# ESP32_MCU.net
KiCad netlist of a schematic drawn in Altium Designer
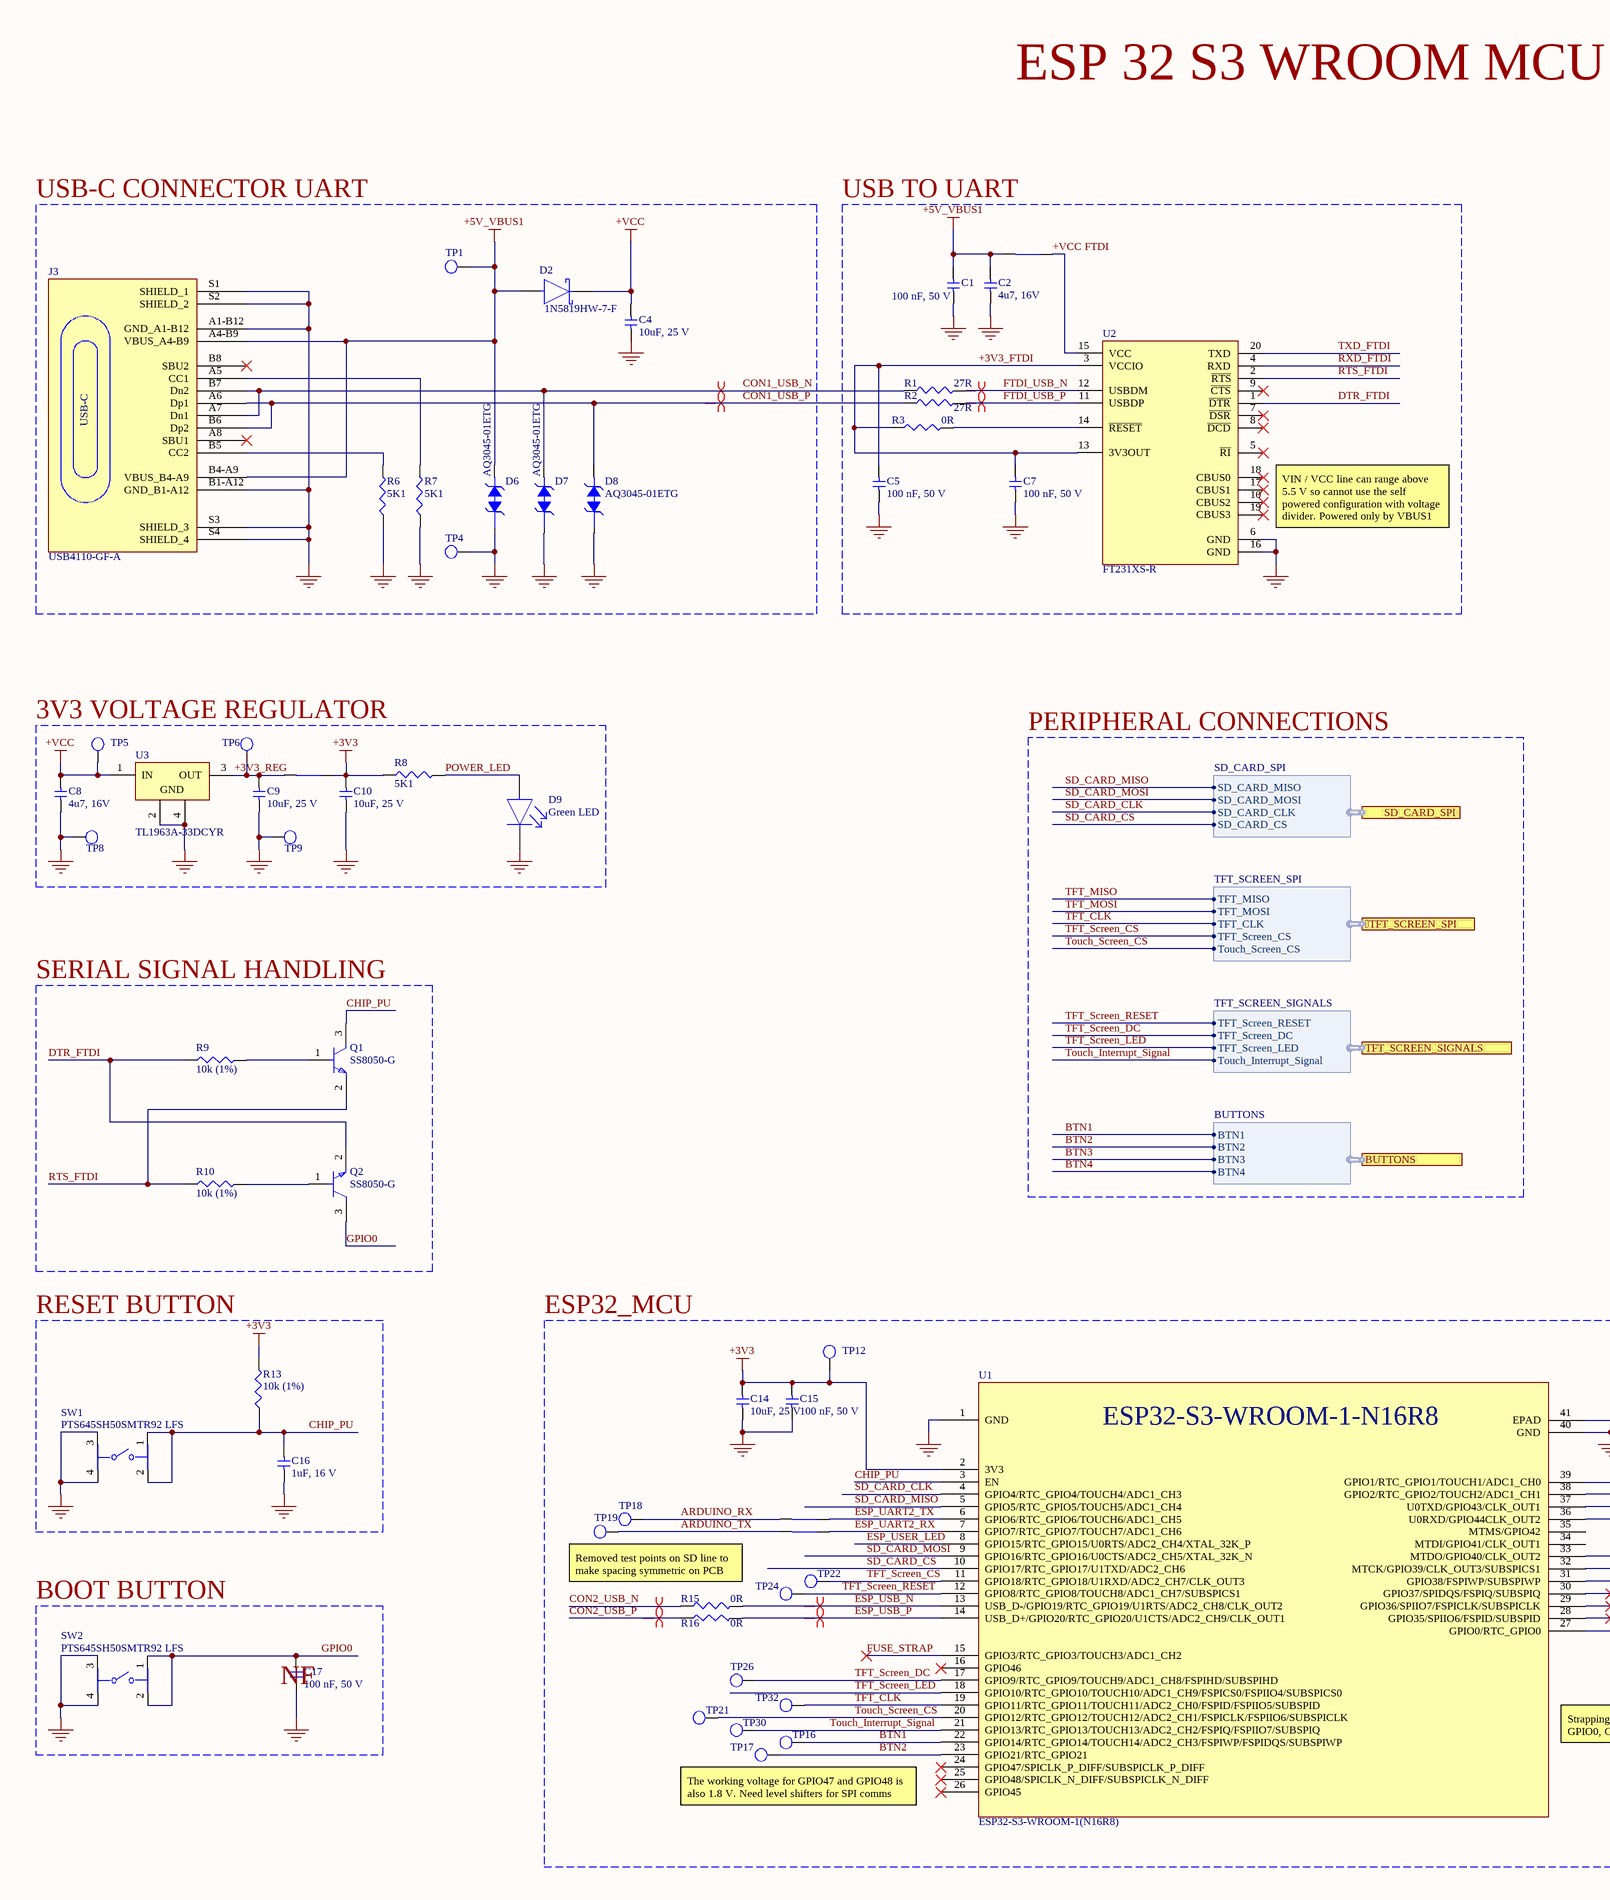
[diagram p0: ESP32_MCU.SchDoc, left]
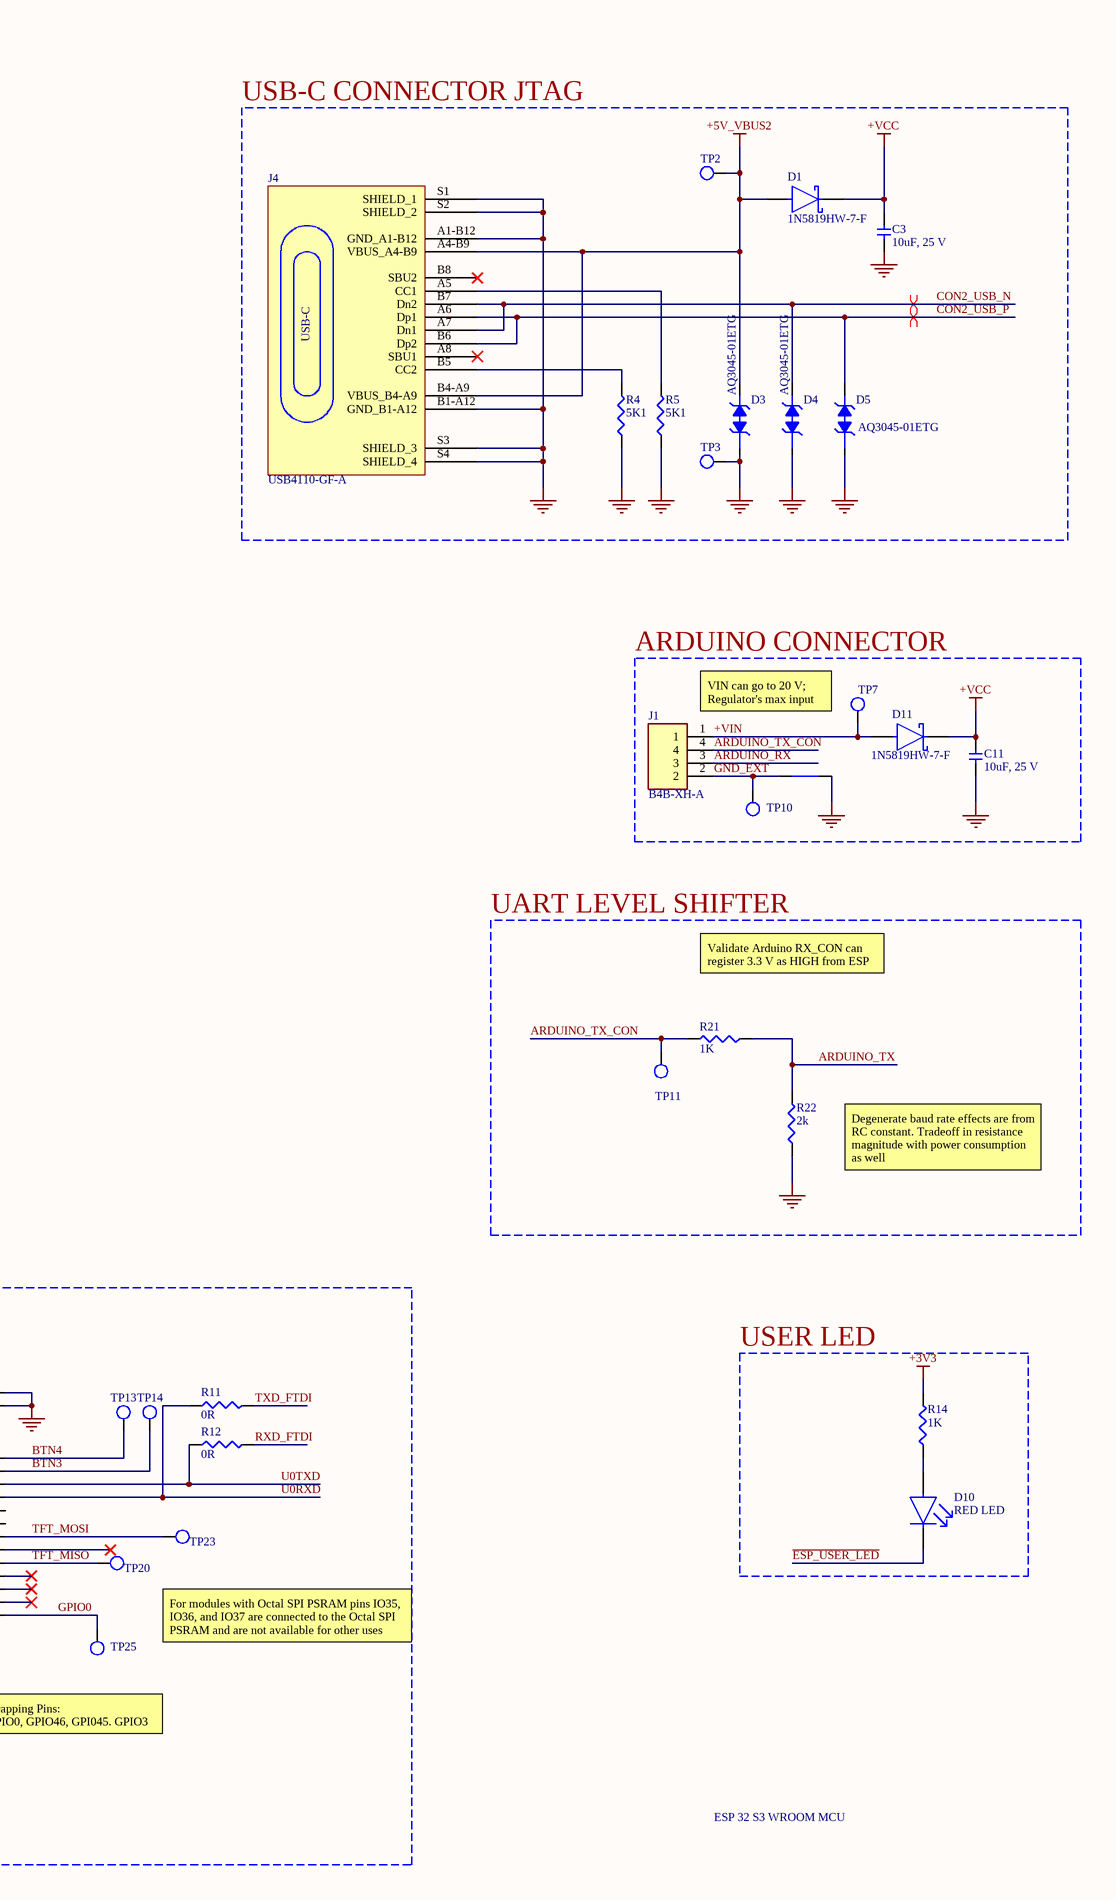
[diagram p1: ESP32_MCU.SchDoc, right]

(export (version "E")
  (design (tool "Eeschema 10.0.6"))
  (components
    (comp (ref "C1")
      (value "100 nF, 50 V")
      (footprint "0805_CAP")
      (fields
        (field (name "MANUFACTURER") "Walsin Technologies")
        (field (name "MANUFACTURER PART NUMBER") "1206B104K500CT")
      )
      (libsource (lib "SchLib") (part "1206B104K500CT"))
    )
    (comp (ref "C2")
      (value "4u7, 16V")
      (footprint "0805_CAP")
      (description "CAP CER 4.7UF 16V X7R 1206")
      (fields
        (field (name "MANUFACTURER") "Samsung")
        (field (name "MANUFACTURER PART NUMBER") "CL31B475KOHNNNE")
      )
      (libsource (lib "SchLib") (part "CL31B475KOHNNNE"))
    )
    (comp (ref "C3")
      (value "10uF, 25 V")
      (footprint "0805_CAP")
      (fields
        (field (name "MANUFACTURER") "Taiyo Yuden")
        (field (name "MANUFACTURER PART NUMBER") "TMK316BJ106KL-T")
      )
      (libsource (lib "SchLib") (part "TMK316BJ106KL-T"))
    )
    (comp (ref "C4")
      (value "10uF, 25 V")
      (footprint "0805_CAP")
      (fields
        (field (name "MANUFACTURER") "Taiyo Yuden")
        (field (name "MANUFACTURER PART NUMBER") "TMK316BJ106KL-T")
      )
      (libsource (lib "SchLib") (part "TMK316BJ106KL-T"))
    )
    (comp (ref "C5")
      (value "100 nF, 50 V")
      (footprint "0805_CAP")
      (fields
        (field (name "MANUFACTURER") "Walsin Technologies")
        (field (name "MANUFACTURER PART NUMBER") "1206B104K500CT")
      )
      (libsource (lib "SchLib") (part "1206B104K500CT"))
    )
    (comp (ref "C7")
      (value "100 nF, 50 V")
      (footprint "0805_CAP")
      (fields
        (field (name "MANUFACTURER") "Walsin Technologies")
        (field (name "MANUFACTURER PART NUMBER") "1206B104K500CT")
      )
      (libsource (lib "SchLib") (part "1206B104K500CT"))
    )
    (comp (ref "C8")
      (value "4u7, 16V")
      (footprint "0805_CAP")
      (description "CAP CER 4.7UF 16V X7R 1206")
      (fields
        (field (name "MANUFACTURER") "Samsung")
        (field (name "MANUFACTURER PART NUMBER") "CL31B475KOHNNNE")
      )
      (libsource (lib "SchLib") (part "CL31B475KOHNNNE"))
    )
    (comp (ref "C9")
      (value "10uF, 25 V")
      (footprint "0805_CAP")
      (fields
        (field (name "MANUFACTURER") "Taiyo Yuden")
        (field (name "MANUFACTURER PART NUMBER") "TMK316BJ106KL-T")
      )
      (libsource (lib "SchLib") (part "TMK316BJ106KL-T"))
    )
    (comp (ref "C10")
      (value "10uF, 25 V")
      (footprint "0805_CAP")
      (fields
        (field (name "MANUFACTURER") "Taiyo Yuden")
        (field (name "MANUFACTURER PART NUMBER") "TMK316BJ106KL-T")
      )
      (libsource (lib "SchLib") (part "TMK316BJ106KL-T"))
    )
    (comp (ref "C11")
      (value "10uF, 25 V")
      (footprint "0805_CAP")
      (fields
        (field (name "MANUFACTURER") "Taiyo Yuden")
        (field (name "MANUFACTURER PART NUMBER") "TMK316BJ106KL-T")
      )
      (libsource (lib "SchLib") (part "TMK316BJ106KL-T"))
    )
    (comp (ref "C14")
      (value "10uF, 25 V")
      (footprint "0805_CAP")
      (fields
        (field (name "MANUFACTURER") "Taiyo Yuden")
        (field (name "MANUFACTURER PART NUMBER") "TMK316BJ106KL-T")
      )
      (libsource (lib "SchLib") (part "TMK316BJ106KL-T"))
    )
    (comp (ref "C15")
      (value "100 nF, 50 V")
      (footprint "0805_CAP")
      (fields
        (field (name "MANUFACTURER") "Walsin Technologies")
        (field (name "MANUFACTURER PART NUMBER") "1206B104K500CT")
      )
      (libsource (lib "SchLib") (part "1206B104K500CT"))
    )
    (comp (ref "C16")
      (value "1uF, 16 V")
      (footprint "0805_CAP")
      (libsource (lib "SchLib") (part "CL31B105KOFNNNE"))
    )
    (comp (ref "C17")
      (value "100 nF, 50 V")
      (footprint "0805_CAP")
      (fields
        (field (name "MANUFACTURER") "Walsin Technologies")
        (field (name "MANUFACTURER PART NUMBER") "1206B104K500CT")
      )
      (libsource (lib "SchLib") (part "1206B104K500CT"))
    )
    (comp (ref "D1")
      (value "1N5819HW-7-F")
      (footprint "FP-SOD123-IPC_B")
      (description "Rectifier Diode, Schottky, 1 Phase, 1 Element, 1A, 40V V(RRM), Silicon")
      (fields (field (name "MANUFACTURER") "Diodes"))
      (libsource (lib "SchLib") (part "1N5819HW-7-F"))
    )
    (comp (ref "D2")
      (value "1N5819HW-7-F")
      (footprint "FP-SOD123-IPC_B")
      (description "Rectifier Diode, Schottky, 1 Phase, 1 Element, 1A, 40V V(RRM), Silicon")
      (fields (field (name "MANUFACTURER") "Diodes"))
      (libsource (lib "SchLib") (part "1N5819HW-7-F"))
    )
    (comp (ref "D3")
      (value "AQ3045-01ETG")
      (footprint "SOD882")
      (libsource (lib "SchLib") (part "AQ3045-01ETG"))
    )
    (comp (ref "D4")
      (value "AQ3045-01ETG")
      (footprint "SOD882")
      (libsource (lib "SchLib") (part "AQ3045-01ETG"))
    )
    (comp (ref "D5")
      (value "AQ3045-01ETG")
      (footprint "SOD882")
      (libsource (lib "SchLib") (part "AQ3045-01ETG"))
    )
    (comp (ref "D6")
      (value "AQ3045-01ETG")
      (footprint "SOD882")
      (libsource (lib "SchLib") (part "AQ3045-01ETG"))
    )
    (comp (ref "D7")
      (value "AQ3045-01ETG")
      (footprint "SOD882")
      (libsource (lib "SchLib") (part "AQ3045-01ETG"))
    )
    (comp (ref "D8")
      (value "AQ3045-01ETG")
      (footprint "SOD882")
      (libsource (lib "SchLib") (part "AQ3045-01ETG"))
    )
    (comp (ref "D9")
      (value "Green LED")
      (footprint "FP-LTST-C171KGKT-MFG")
      (description "Green 571nm LED Indication - Discrete 2V 0805 (2012 Metric)")
      (fields
        (field (name "MANUFACTURER") "Vishay Lite-On")
        (field (name "MANUFACTURER PART NUMBER") "LTST-C171KGKT")
      )
      (libsource (lib "SchLib") (part "LTST-C171KGKT"))
    )
    (comp (ref "D10")
      (value "RED LED")
      (footprint "LTST-C170KRKT_V")
      (description "Red 631nm LED Indication - Discrete 2V 0805 (2012 Metric)")
      (fields
        (field (name "MANUFACTURER") "Vishay Lite-On")
        (field (name "MANUFACTURER PART NUMBER") "LTST-C171KRKT")
      )
      (libsource (lib "SchLib") (part "LTST-C171KRKT"))
    )
    (comp (ref "D11")
      (value "1N5819HW-7-F")
      (footprint "FP-SOD123-IPC_B")
      (description "Rectifier Diode, Schottky, 1 Phase, 1 Element, 1A, 40V V(RRM), Silicon")
      (fields (field (name "MANUFACTURER") "Diodes"))
      (libsource (lib "SchLib") (part "1N5819HW-7-F"))
    )
    (comp (ref "J1")
      (value "B4B-XH-A")
      (footprint "JST_B4B-XH-A(LF)(SN)")
      (description "CONN HEADER VERT 4POS 2.5MM")
      (fields (field (name "MANUFACTURER") "JST") (field (name "MANUFACTURER PART NUMBER") "S4B-PH-K-S"))
      (libsource (lib "SchLib") (part "455-B4B-XH-A-ND"))
    )
    (comp (ref "J3")
      (value "USB4110-GF-A")
      (footprint "FP-USB4110-GF-A-MFG")
      (libsource (lib "SchLib") (part "USB4110-GF-A"))
    )
    (comp (ref "J4")
      (value "USB4110-GF-A")
      (footprint "FP-USB4110-GF-A-MFG")
      (libsource (lib "SchLib") (part "USB4110-GF-A"))
    )
    (comp (ref "NT1")
      (value "NT")
      (footprint "NetTie_SMD")
      (description "Net TIE SMD")
      (libsource (lib "SchLib") (part "NetTie_SMD"))
    )
    (comp (ref "NT2")
      (value "NT")
      (footprint "NetTie_SMD")
      (description "Net TIE SMD")
      (libsource (lib "SchLib") (part "NetTie_SMD"))
    )
    (comp (ref "NT3")
      (value "NT")
      (footprint "NetTie_SMD")
      (description "Net TIE SMD")
      (libsource (lib "SchLib") (part "NetTie_SMD"))
    )
    (comp (ref "NT6")
      (value "NT")
      (footprint "NetTie_SMD")
      (description "Net TIE SMD")
      (libsource (lib "SchLib") (part "NetTie_SMD"))
    )
    (comp (ref "NT8")
      (value "NT")
      (footprint "NetTie_SMD")
      (description "Net TIE SMD")
      (libsource (lib "SchLib") (part "NetTie_SMD"))
    )
    (comp (ref "Q1")
      (value "SS8050-G")
      (footprint "FP-SS8050-G-IPC_A")
      (description "Bipolar (BJT) Transistor NPN 25 V 1.5 A 100MHz 300 mW Surface Mount SOT-23-3")
      (fields (field (name "MANUFACTURER") "Comchip"))
      (libsource (lib "SchLib") (part "SS8050-G"))
    )
    (comp (ref "Q2")
      (value "SS8050-G")
      (footprint "FP-SS8050-G-IPC_A")
      (description "Bipolar (BJT) Transistor NPN 25 V 1.5 A 100MHz 300 mW Surface Mount SOT-23-3")
      (fields (field (name "MANUFACTURER") "Comchip"))
      (libsource (lib "SchLib") (part "SS8050-G"))
    )
    (comp (ref "R1")
      (value "27R")
      (footprint "0805_Resistor")
      (description "RES SMD 27.4 OHM 1% 1/8W 0805")
      (fields
        (field (name "MANUFACTURER") "Vishay")
        (field (name "MANUFACTURER PART NUMBER") "CRCW080527R4FKEA")
      )
      (libsource (lib "SchLib") (part "CRCW080527R4FKEA"))
    )
    (comp (ref "R2")
      (value "27R")
      (footprint "0805_Resistor")
      (description "RES SMD 27.4 OHM 1% 1/8W 0805")
      (fields
        (field (name "MANUFACTURER") "Vishay")
        (field (name "MANUFACTURER PART NUMBER") "CRCW080527R4FKEA")
      )
      (libsource (lib "SchLib") (part "CRCW080527R4FKEA"))
    )
    (comp (ref "R3")
      (value "0R")
      (footprint "0805_Resistor")
      (fields
        (field (name "MANUFACTURER") "Bourns")
        (field (name "MANUFACTURER PART NUMBER") "CR0805AJ/-000EAS")
      )
      (libsource (lib "SchLib") (part "CR0805AJ/-000EAS"))
    )
    (comp (ref "R4")
      (value "5K1")
      (footprint "0805_Resistor")
      (description "RES 5.1K OHM 5% 1/8W 0805")
      (fields (field (name "TOLERANCE") "5%") (field (name "MANUFACTURER") "Yageo"))
      (libsource (lib "SchLib") (part "RC0805JR-075K1L"))
    )
    (comp (ref "R5")
      (value "5K1")
      (footprint "0805_Resistor")
      (description "RES 5.1K OHM 5% 1/8W 0805")
      (fields (field (name "TOLERANCE") "5%") (field (name "MANUFACTURER") "Yageo"))
      (libsource (lib "SchLib") (part "RC0805JR-075K1L"))
    )
    (comp (ref "R6")
      (value "5K1")
      (footprint "0805_Resistor")
      (description "RES 5.1K OHM 5% 1/8W 0805")
      (fields (field (name "TOLERANCE") "5%") (field (name "MANUFACTURER") "Yageo"))
      (libsource (lib "SchLib") (part "RC0805JR-075K1L"))
    )
    (comp (ref "R7")
      (value "5K1")
      (footprint "0805_Resistor")
      (description "RES 5.1K OHM 5% 1/8W 0805")
      (fields (field (name "TOLERANCE") "5%") (field (name "MANUFACTURER") "Yageo"))
      (libsource (lib "SchLib") (part "RC0805JR-075K1L"))
    )
    (comp (ref "R8")
      (value "5K1")
      (footprint "0805_Resistor")
      (description "RES 5.1K OHM 5% 1/8W 0805")
      (fields
        (field (name "MANUFACTURER") "Yageo")
        (field (name "MANUFACTURER PART NUMBER") "RC0805JR-075K1L")
      )
      (libsource (lib "SchLib") (part "RC0805JR-075K1L"))
    )
    (comp (ref "R9")
      (value "10k (1%)")
      (footprint "0805_Resistor")
      (fields (field (name "TOLERANCE") "1%"))
      (libsource (lib "SchLib") (part "RMCF0805FT10K0"))
    )
    (comp (ref "R10")
      (value "10k (1%)")
      (footprint "0805_Resistor")
      (fields (field (name "TOLERANCE") "1%"))
      (libsource (lib "SchLib") (part "RMCF0805FT10K0"))
    )
    (comp (ref "R11")
      (value "0R")
      (footprint "0805_Resistor")
      (fields
        (field (name "MANUFACTURER") "Bourns")
        (field (name "MANUFACTURER PART NUMBER") "CR0805AJ/-000EAS")
      )
      (libsource (lib "SchLib") (part "CR0805AJ/-000EAS"))
    )
    (comp (ref "R12")
      (value "0R")
      (footprint "0805_Resistor")
      (fields
        (field (name "MANUFACTURER") "Bourns")
        (field (name "MANUFACTURER PART NUMBER") "CR0805AJ/-000EAS")
      )
      (libsource (lib "SchLib") (part "CR0805AJ/-000EAS"))
    )
    (comp (ref "R13")
      (value "10k (1%)")
      (footprint "0805_Resistor")
      (fields (field (name "TOLERANCE") "1%"))
      (libsource (lib "SchLib") (part "RMCF0805FT10K0"))
    )
    (comp (ref "R14")
      (value "1K")
      (footprint "0805_Resistor")
      (description "RES 1K OHM 1% 1/8W 0805")
      (fields
        (field (name "MANUFACTURER") "Yageo")
        (field (name "MANUFACTURER PART NUMBER") "RC0805FR-071KL")
      )
      (libsource (lib "SchLib") (part "RC0805FR-071KL"))
    )
    (comp (ref "R15")
      (value "0R")
      (footprint "0805_Resistor")
      (fields
        (field (name "MANUFACTURER") "Bourns")
        (field (name "MANUFACTURER PART NUMBER") "CR0805AJ/-000EAS")
      )
      (libsource (lib "SchLib") (part "CR0805AJ/-000EAS"))
    )
    (comp (ref "R16")
      (value "0R")
      (footprint "0805_Resistor")
      (fields
        (field (name "MANUFACTURER") "Bourns")
        (field (name "MANUFACTURER PART NUMBER") "CR0805AJ/-000EAS")
      )
      (libsource (lib "SchLib") (part "CR0805AJ/-000EAS"))
    )
    (comp (ref "R21")
      (value "1K")
      (footprint "0805_Resistor")
      (description "RES 1K OHM 1% 1/8W 0805")
      (fields
        (field (name "MANUFACTURER") "Yageo")
        (field (name "MANUFACTURER PART NUMBER") "RC0805FR-071KL")
      )
      (libsource (lib "SchLib") (part "RC0805FR-071KL"))
    )
    (comp (ref "R22")
      (value "2k")
      (footprint "0805_Resistor")
      (fields
        (field (name "MANUFACTURER") "Vishay")
        (field (name "MANUFACTURER PART NUMBER") "CRCW08052K00FKEA")
        (field (name "TOLERANCE") "1%")
      )
      (libsource (lib "SchLib") (part "CRCW08052K00FKEA"))
    )
    (comp (ref "SW1")
      (value "PTS645SH50SMTR92 LFS")
      (footprint "FP-PTS645SH50SMTR92LFS-MFG")
      (description "Tactile Switch SPST-NO Top Actuated Surface Mount")
      (libsource (lib "SchLib") (part "PTS645SH50SMTR92 LFS"))
    )
    (comp (ref "SW2")
      (value "PTS645SH50SMTR92 LFS")
      (footprint "FP-PTS645SH50SMTR92LFS-MFG")
      (description "Tactile Switch SPST-NO Top Actuated Surface Mount")
      (libsource (lib "SchLib") (part "PTS645SH50SMTR92 LFS"))
    )
    (comp (ref "TP1")
      (value "Test Point")
      (footprint "Probe-Point")
      (description "Generic Test Point")
      (libsource (lib "University of Calgary Solar Car Team") (part "Test Point-Symbol-1"))
    )
    (comp (ref "TP2")
      (value "Test Point")
      (footprint "Probe-Point")
      (description "Generic Test Point")
      (libsource (lib "University of Calgary Solar Car Team") (part "Test Point-Symbol-1"))
    )
    (comp (ref "TP3")
      (value "Test Point")
      (footprint "Probe-Point")
      (description "Generic Test Point")
      (libsource (lib "University of Calgary Solar Car Team") (part "Test Point-Symbol-1"))
    )
    (comp (ref "TP4")
      (value "Test Point")
      (footprint "Probe-Point")
      (description "Generic Test Point")
      (libsource (lib "University of Calgary Solar Car Team") (part "Test Point-Symbol-1"))
    )
    (comp (ref "TP5")
      (value "Test Point")
      (footprint "Probe-Point")
      (description "Generic Test Point")
      (libsource (lib "University of Calgary Solar Car Team") (part "Test Point-Symbol-1"))
    )
    (comp (ref "TP6")
      (value "Test Point")
      (footprint "Probe-Point")
      (description "Generic Test Point")
      (libsource (lib "University of Calgary Solar Car Team") (part "Test Point-Symbol-1"))
    )
    (comp (ref "TP7")
      (value "Test Point")
      (footprint "Probe-Point")
      (description "Generic Test Point")
      (libsource (lib "University of Calgary Solar Car Team") (part "Test Point-Symbol-1"))
    )
    (comp (ref "TP8")
      (value "Test Point")
      (footprint "Probe-Point")
      (description "Generic Test Point")
      (libsource (lib "University of Calgary Solar Car Team") (part "Test Point-Symbol-1"))
    )
    (comp (ref "TP9")
      (value "Test Point")
      (footprint "Probe-Point")
      (description "Generic Test Point")
      (libsource (lib "University of Calgary Solar Car Team") (part "Test Point-Symbol-1"))
    )
    (comp (ref "TP10")
      (value "Test Point")
      (footprint "Probe-Point")
      (description "Generic Test Point")
      (libsource (lib "University of Calgary Solar Car Team") (part "Test Point-Symbol-1"))
    )
    (comp (ref "TP11")
      (value "Test Point")
      (footprint "Probe-Point")
      (description "Generic Test Point")
      (libsource (lib "University of Calgary Solar Car Team") (part "Test Point-Symbol-1"))
    )
    (comp (ref "TP12")
      (value "Test Point")
      (footprint "Probe-Point")
      (description "Generic Test Point")
      (libsource (lib "University of Calgary Solar Car Team") (part "Test Point-Symbol-1"))
    )
    (comp (ref "TP13")
      (value "Test Point")
      (footprint "Probe-Point")
      (description "Generic Test Point")
      (libsource (lib "University of Calgary Solar Car Team") (part "Test Point-Symbol-1"))
    )
    (comp (ref "TP14")
      (value "Test Point")
      (footprint "Probe-Point")
      (description "Generic Test Point")
      (libsource (lib "University of Calgary Solar Car Team") (part "Test Point-Symbol-1"))
    )
    (comp (ref "TP16")
      (value "Test Point")
      (footprint "Probe-Point")
      (description "Generic Test Point")
      (libsource (lib "University of Calgary Solar Car Team") (part "Test Point-Symbol-1"))
    )
    (comp (ref "TP17")
      (value "Test Point")
      (footprint "Probe-Point")
      (description "Generic Test Point")
      (libsource (lib "University of Calgary Solar Car Team") (part "Test Point-Symbol-1"))
    )
    (comp (ref "TP18")
      (value "Test Point")
      (footprint "Probe-Point")
      (description "Generic Test Point")
      (libsource (lib "University of Calgary Solar Car Team") (part "Test Point-Symbol-1"))
    )
    (comp (ref "TP19")
      (value "Test Point")
      (footprint "Probe-Point")
      (description "Generic Test Point")
      (libsource (lib "University of Calgary Solar Car Team") (part "Test Point-Symbol-1"))
    )
    (comp (ref "TP20")
      (value "Test Point")
      (footprint "Probe-Point")
      (description "Generic Test Point")
      (libsource (lib "University of Calgary Solar Car Team") (part "Test Point-Symbol-1"))
    )
    (comp (ref "TP21")
      (value "Test Point")
      (footprint "Probe-Point")
      (description "Generic Test Point")
      (libsource (lib "University of Calgary Solar Car Team") (part "Test Point-Symbol-1"))
    )
    (comp (ref "TP22")
      (value "Test Point")
      (footprint "Probe-Point")
      (description "Generic Test Point")
      (libsource (lib "University of Calgary Solar Car Team") (part "Test Point-Symbol-1"))
    )
    (comp (ref "TP23")
      (value "Test Point")
      (footprint "Probe-Point")
      (description "Generic Test Point")
      (libsource (lib "University of Calgary Solar Car Team") (part "Test Point-Symbol-1"))
    )
    (comp (ref "TP24")
      (value "Test Point")
      (footprint "Probe-Point")
      (description "Generic Test Point")
      (libsource (lib "University of Calgary Solar Car Team") (part "Test Point-Symbol-1"))
    )
    (comp (ref "TP25")
      (value "Test Point")
      (footprint "Probe-Point")
      (description "Generic Test Point")
      (libsource (lib "University of Calgary Solar Car Team") (part "Test Point-Symbol-1"))
    )
    (comp (ref "TP26")
      (value "Test Point")
      (footprint "Probe-Point")
      (description "Generic Test Point")
      (libsource (lib "University of Calgary Solar Car Team") (part "Test Point-Symbol-1"))
    )
    (comp (ref "TP30")
      (value "Test Point")
      (footprint "Probe-Point")
      (description "Generic Test Point")
      (libsource (lib "University of Calgary Solar Car Team") (part "Test Point-Symbol-1"))
    )
    (comp (ref "TP32")
      (value "Test Point")
      (footprint "Probe-Point")
      (description "Generic Test Point")
      (libsource (lib "University of Calgary Solar Car Team") (part "Test Point-Symbol-1"))
    )
    (comp (ref "U1")
      (value "ESP32-S3-WROOM-1(N16R8)")
      (footprint "ESP32S3WROOM1N8R2")
      (description "RF TXRX MOD BT WIFI PCB TH SMD")
      (fields (field (name "MANUFACTURER") "Espressif Systems"))
      (libsource (lib "SchLib") (part "ESP32-S3-WROOM-1(N16R8)"))
    )
    (comp (ref "U2")
      (value "FT231XS-R")
      (footprint "FP-SSOP-20-IPC_A")
      (description "IC USB SERIAL FULL UART 20SSOP")
      (fields (field (name "MANUFACTURER") "FTDI"))
      (libsource (lib "SchLib") (part "FT231XS-R"))
    )
    (comp (ref "U3")
      (value "TL1963A-33DCYR")
      (footprint "DCY0004A_N")
      (description "Linear Voltage Regulator IC Positive Fixed 1 Output 1.5A SOT-223-4")
      (fields (field (name "MANUFACTURER") "Texas Instruments"))
      (libsource (lib "SchLib") (part "TL1963A-33DCYR"))
    )
  )
  (nets
    (net (code "5") (name "+3V3") (class "Default")
      (node (ref "C10") (pin "2") (pinfunction "2_2") (pintype "passive"))
      (node (ref "C14") (pin "2") (pinfunction "2_2") (pintype "passive"))
      (node (ref "C15") (pin "2") (pinfunction "2_2") (pintype "passive"))
      (node (ref "NT3") (pin "2") (pinfunction "10_2") (pintype "passive"))
      (node (ref "R13") (pin "2") (pinfunction "2_2") (pintype "passive"))
      (node (ref "R14") (pin "2") (pinfunction "2_2") (pintype "passive"))
      (node (ref "R8") (pin "1") (pinfunction "1_1") (pintype "passive"))
      (node (ref "TP12") (pin "1") (pinfunction "1_1") (pintype "passive"))
      (node (ref "U1") (pin "2") (pinfunction "3V3_2") (pintype "passive"))
    )
    (net (code "6") (name "+5V_VBUS1") (class "Default")
      (node (ref "C1") (pin "2") (pinfunction "2_2") (pintype "passive"))
      (node (ref "C2") (pin "2") (pinfunction "2_2") (pintype "passive"))
      (node (ref "D2") (pin "2") (pinfunction "A_2") (pintype "passive"))
      (node (ref "D6") (pin "1") (pinfunction "1_1") (pintype "passive"))
      (node (ref "J3") (pin "A4-B9") (pinfunction "VBUS_A4-B9_A4-B9") (pintype "passive"))
      (node (ref "J3") (pin "B4-A9") (pinfunction "VBUS_B4-A9_B4-A9") (pintype "passive"))
      (node (ref "NT6") (pin "1") (pinfunction "9_1") (pintype "passive"))
      (node (ref "TP1") (pin "1") (pinfunction "1_1") (pintype "passive"))
    )
    (net (code "7") (name "+5V_VBUS2") (class "Default")
      (node (ref "D1") (pin "2") (pinfunction "A_2") (pintype "passive"))
      (node (ref "D3") (pin "1") (pinfunction "1_1") (pintype "passive"))
      (node (ref "J4") (pin "A4-B9") (pinfunction "VBUS_A4-B9_A4-B9") (pintype "passive"))
      (node (ref "J4") (pin "B4-A9") (pinfunction "VBUS_B4-A9_B4-A9") (pintype "passive"))
      (node (ref "TP2") (pin "1") (pinfunction "1_1") (pintype "passive"))
    )
    (net (code "8") (name "+VCC") (class "Default")
      (node (ref "C11") (pin "2") (pinfunction "2_2") (pintype "passive"))
      (node (ref "C3") (pin "2") (pinfunction "2_2") (pintype "passive"))
      (node (ref "C4") (pin "2") (pinfunction "2_2") (pintype "passive"))
      (node (ref "C8") (pin "2") (pinfunction "2_2") (pintype "passive"))
      (node (ref "D1") (pin "1") (pinfunction "C_1") (pintype "passive"))
      (node (ref "D11") (pin "1") (pinfunction "C_1") (pintype "passive"))
      (node (ref "D2") (pin "1") (pinfunction "C_1") (pintype "passive"))
      (node (ref "TP5") (pin "1") (pinfunction "1_1") (pintype "passive"))
      (node (ref "U3") (pin "1") (pinfunction "IN_1") (pintype "power_in"))
    )
    (net (code "9") (name "/+3V3_FTDI") (class "Default")
      (node (ref "C5") (pin "2") (pinfunction "2_2") (pintype "passive"))
      (node (ref "C7") (pin "2") (pinfunction "2_2") (pintype "passive"))
      (node (ref "R3") (pin "1") (pinfunction "1_1") (pintype "passive"))
      (node (ref "U2") (pin "13") (pinfunction "3V3OUT_13") (pintype "passive"))
      (node (ref "U2") (pin "3") (pinfunction "VCCIO_3") (pintype "passive"))
    )
    (net (code "10") (name "/+3V3_REG") (class "Default")
      (node (ref "C9") (pin "2") (pinfunction "2_2") (pintype "passive"))
      (node (ref "NT3") (pin "1") (pinfunction "9_1") (pintype "passive"))
      (node (ref "TP6") (pin "1") (pinfunction "1_1") (pintype "passive"))
      (node (ref "U3") (pin "3") (pinfunction "OUT_3") (pintype "power_in"))
    )
    (net (code "11") (name "/+VCC FTDI") (class "Default")
      (node (ref "NT6") (pin "2") (pinfunction "10_2") (pintype "passive"))
      (node (ref "U2") (pin "15") (pinfunction "VCC_15") (pintype "passive"))
    )
    (net (code "12") (name "/+VIN") (class "Default")
      (node (ref "D11") (pin "2") (pinfunction "A_2") (pintype "passive"))
      (node (ref "J1") (pin "1") (pinfunction "1_1") (pintype "passive"))
      (node (ref "TP7") (pin "1") (pinfunction "1_1") (pintype "passive"))
    )
    (net (code "13") (name "/ARDUINO_RX") (class "Default")
      (node (ref "J1") (pin "3") (pinfunction "3_3") (pintype "passive"))
      (node (ref "NT1") (pin "1") (pinfunction "9_1") (pintype "passive"))
      (node (ref "TP18") (pin "1") (pinfunction "1_1") (pintype "passive"))
    )
    (net (code "14") (name "/ARDUINO_TX") (class "Default")
      (node (ref "NT2") (pin "1") (pinfunction "9_1") (pintype "passive"))
      (node (ref "R21") (pin "1") (pinfunction "1_1") (pintype "passive"))
      (node (ref "R22") (pin "2") (pinfunction "2_2") (pintype "passive"))
      (node (ref "TP19") (pin "1") (pinfunction "1_1") (pintype "passive"))
    )
    (net (code "15") (name "/ARDUINO_TX_CON") (class "Default")
      (node (ref "J1") (pin "4") (pinfunction "4_4") (pintype "passive"))
      (node (ref "R21") (pin "2") (pinfunction "2_2") (pintype "passive"))
      (node (ref "TP11") (pin "1") (pinfunction "1_1") (pintype "passive"))
    )
    (net (code "16") (name "/BTN1") (class "Default")
      (node (ref "TP16") (pin "1") (pinfunction "1_1") (pintype "passive"))
      (node (ref "U1") (pin "22") (pinfunction "GPIO14/RTC_GPIO14/TOUCH14/ADC2_CH3/FSPIWP/FSPIDQS/SUBSPIWP_22") (pintype "passive"))
    )
    (net (code "17") (name "/BTN2") (class "Default")
      (node (ref "TP17") (pin "1") (pinfunction "1_1") (pintype "passive"))
      (node (ref "U1") (pin "23") (pinfunction "GPIO21/RTC_GPIO21_23") (pintype "passive"))
    )
    (net (code "18") (name "/BTN3") (class "Default")
      (node (ref "TP14") (pin "1") (pinfunction "1_1") (pintype "passive"))
      (node (ref "U1") (pin "38") (pinfunction "GPIO2/RTC_GPIO2/TOUCH2/ADC1_CH1_38") (pintype "passive"))
    )
    (net (code "19") (name "/BTN4") (class "Default")
      (node (ref "TP13") (pin "1") (pinfunction "1_1") (pintype "passive"))
      (node (ref "U1") (pin "39") (pinfunction "GPIO1/RTC_GPIO1/TOUCH1/ADC1_CH0_39") (pintype "passive"))
    )
    (net (code "20") (name "/CHIP_PU") (class "Default")
      (node (ref "C16") (pin "2") (pinfunction "2_2") (pintype "passive"))
      (node (ref "Q1") (pin "3") (pinfunction "C_3") (pintype "passive"))
      (node (ref "R13") (pin "1") (pinfunction "1_1") (pintype "passive"))
      (node (ref "SW1") (pin "1") (pinfunction "1_1") (pintype "passive"))
      (node (ref "SW1") (pin "2") (pinfunction "2_2") (pintype "passive"))
      (node (ref "U1") (pin "3") (pinfunction "EN_3") (pintype "passive"))
    )
    (net (code "21") (name "/CON1_USB_N") (class "Default")
      (node (ref "D7") (pin "1") (pinfunction "1_1") (pintype "passive"))
      (node (ref "J3") (pin "A7") (pinfunction "Dn1_A7") (pintype "passive"))
      (node (ref "J3") (pin "B7") (pinfunction "Dn2_B7") (pintype "passive"))
      (node (ref "R1") (pin "1") (pinfunction "1_1") (pintype "passive"))
    )
    (net (code "22") (name "/CON1_USB_P") (class "Default")
      (node (ref "D8") (pin "1") (pinfunction "1_1") (pintype "passive"))
      (node (ref "J3") (pin "A6") (pinfunction "Dp1_A6") (pintype "passive"))
      (node (ref "J3") (pin "B6") (pinfunction "Dp2_B6") (pintype "passive"))
      (node (ref "R2") (pin "1") (pinfunction "1_1") (pintype "passive"))
    )
    (net (code "23") (name "/CON2_USB_N") (class "Default")
      (node (ref "D4") (pin "1") (pinfunction "1_1") (pintype "passive"))
      (node (ref "J4") (pin "A7") (pinfunction "Dn1_A7") (pintype "passive"))
      (node (ref "J4") (pin "B7") (pinfunction "Dn2_B7") (pintype "passive"))
      (node (ref "R15") (pin "1") (pinfunction "1_1") (pintype "passive"))
    )
    (net (code "24") (name "/CON2_USB_P") (class "Default")
      (node (ref "D5") (pin "1") (pinfunction "1_1") (pintype "passive"))
      (node (ref "J4") (pin "A6") (pinfunction "Dp1_A6") (pintype "passive"))
      (node (ref "J4") (pin "B6") (pinfunction "Dp2_B6") (pintype "passive"))
      (node (ref "R16") (pin "1") (pinfunction "1_1") (pintype "passive"))
    )
    (net (code "25") (name "/DTR_FTDI") (class "Default")
      (node (ref "Q2") (pin "2") (pinfunction "E_2") (pintype "passive"))
      (node (ref "R9") (pin "1") (pinfunction "1_1") (pintype "passive"))
      (node (ref "U2") (pin "1") (pinfunction "~{DTR}_1") (pintype "passive"))
    )
    (net (code "26") (name "/ESP_UART2_RX") (class "Default")
      (node (ref "NT2") (pin "2") (pinfunction "10_2") (pintype "passive"))
      (node (ref "U1") (pin "7") (pinfunction "GPIO7/RTC_GPIO7/TOUCH7/ADC1_CH6_7") (pintype "passive"))
    )
    (net (code "27") (name "/ESP_UART2_TX") (class "Default")
      (node (ref "NT1") (pin "2") (pinfunction "10_2") (pintype "passive"))
      (node (ref "U1") (pin "6") (pinfunction "GPIO6/RTC_GPIO6/TOUCH6/ADC1_CH5_6") (pintype "passive"))
    )
    (net (code "28") (name "/ESP_USB_N") (class "Default")
      (node (ref "R15") (pin "2") (pinfunction "2_2") (pintype "passive"))
      (node (ref "U1") (pin "13") (pinfunction "USB_D-/GPIO19/RTC_GPIO19/U1RTS/ADC2_CH8/CLK_OUT2_13") (pintype "passive"))
    )
    (net (code "29") (name "/ESP_USB_P") (class "Default")
      (node (ref "R16") (pin "2") (pinfunction "2_2") (pintype "passive"))
      (node (ref "U1") (pin "14") (pinfunction "USB_D+/GPIO20/RTC_GPIO20/U1CTS/ADC2_CH9/CLK_OUT1_14") (pintype "passive"))
    )
    (net (code "30") (name "/FTDI_USB_N") (class "Default")
      (node (ref "R1") (pin "2") (pinfunction "2_2") (pintype "passive"))
      (node (ref "U2") (pin "12") (pinfunction "USBDM_12") (pintype "passive"))
    )
    (net (code "31") (name "/FTDI_USB_P") (class "Default")
      (node (ref "R2") (pin "2") (pinfunction "2_2") (pintype "passive"))
      (node (ref "U2") (pin "11") (pinfunction "USBDP_11") (pintype "passive"))
    )
    (net (code "32") (name "/FUSE_STRAP") (class "Default")
      (node (ref "U1") (pin "15") (pinfunction "GPIO3/RTC_GPIO3/TOUCH3/ADC1_CH2_15") (pintype "passive+no_connect"))
    )
    (net (code "33") (name "/GND_EXT") (class "Default")
      (node (ref "J1") (pin "2") (pinfunction "2_2") (pintype "passive"))
      (node (ref "NT8") (pin "1") (pinfunction "9_1") (pintype "passive"))
      (node (ref "TP10") (pin "1") (pinfunction "1_1") (pintype "passive"))
    )
    (net (code "34") (name "/GPIO0") (class "Default")
      (node (ref "C17") (pin "2") (pinfunction "2_2") (pintype "passive"))
      (node (ref "Q2") (pin "3") (pinfunction "C_3") (pintype "passive"))
      (node (ref "SW2") (pin "1") (pinfunction "1_1") (pintype "passive"))
      (node (ref "SW2") (pin "2") (pinfunction "2_2") (pintype "passive"))
      (node (ref "TP25") (pin "1") (pinfunction "1_1") (pintype "passive"))
      (node (ref "U1") (pin "27") (pinfunction "GPIO0/RTC_GPIO0_27") (pintype "passive"))
    )
    (net (code "35") (name "/POWER_LED") (class "Default")
      (node (ref "D9") (pin "2") (pinfunction "A_2") (pintype "passive"))
      (node (ref "R8") (pin "2") (pinfunction "2_2") (pintype "passive"))
    )
    (net (code "36") (name "/RTS_FTDI") (class "Default")
      (node (ref "Q1") (pin "2") (pinfunction "E_2") (pintype "passive"))
      (node (ref "R10") (pin "1") (pinfunction "1_1") (pintype "passive"))
      (node (ref "U2") (pin "2") (pinfunction "~{RTS}_2") (pintype "passive"))
    )
    (net (code "37") (name "/RXD_FTDI") (class "Default")
      (node (ref "R12") (pin "2") (pinfunction "2_2") (pintype "passive"))
      (node (ref "U2") (pin "4") (pinfunction "RXD_4") (pintype "passive"))
    )
    (net (code "38") (name "/SD_CARD_CLK") (class "Default")
      (node (ref "U1") (pin "4") (pinfunction "GPIO4/RTC_GPIO4/TOUCH4/ADC1_CH3_4") (pintype "passive"))
    )
    (net (code "39") (name "/SD_CARD_CS") (class "Default")
      (node (ref "U1") (pin "10") (pinfunction "GPIO17/RTC_GPIO17/U1TXD/ADC2_CH6_10") (pintype "passive"))
    )
    (net (code "40") (name "/SD_CARD_MISO") (class "Default")
      (node (ref "U1") (pin "5") (pinfunction "GPIO5/RTC_GPIO5/TOUCH5/ADC1_CH4_5") (pintype "passive"))
    )
    (net (code "41") (name "/SD_CARD_MOSI") (class "Default")
      (node (ref "U1") (pin "9") (pinfunction "GPIO16/RTC_GPIO16/U0CTS/ADC2_CH5/XTAL_32K_N_9") (pintype "passive"))
    )
    (net (code "42") (name "/TFT_CLK") (class "Default")
      (node (ref "TP32") (pin "1") (pinfunction "1_1") (pintype "passive"))
      (node (ref "U1") (pin "19") (pinfunction "GPIO11/RTC_GPIO11/TOUCH11/ADC2_CH0/FSPID/FSPIIO5/SUBSPID_19") (pintype "passive"))
    )
    (net (code "43") (name "/TFT_MISO") (class "Default")
      (node (ref "TP20") (pin "1") (pinfunction "1_1") (pintype "passive"))
      (node (ref "U1") (pin "31") (pinfunction "GPIO38/FSPIWP/SUBSPIWP_31") (pintype "passive"))
    )
    (net (code "44") (name "/TFT_MOSI") (class "Default")
      (node (ref "TP23") (pin "1") (pinfunction "1_1") (pintype "passive"))
      (node (ref "U1") (pin "33") (pinfunction "MTDO/GPIO40/CLK_OUT2_33") (pintype "passive"))
    )
    (net (code "45") (name "/TFT_Screen_CS") (class "Default")
      (node (ref "TP22") (pin "1") (pinfunction "1_1") (pintype "passive"))
      (node (ref "U1") (pin "11") (pinfunction "GPIO18/RTC_GPIO18/U1RXD/ADC2_CH7/CLK_OUT3_11") (pintype "passive"))
    )
    (net (code "46") (name "/TFT_Screen_DC") (class "Default")
      (node (ref "TP26") (pin "1") (pinfunction "1_1") (pintype "passive"))
      (node (ref "U1") (pin "17") (pinfunction "GPIO9/RTC_GPIO9/TOUCH9/ADC1_CH8/FSPIHD/SUBSPIHD_17") (pintype "passive"))
    )
    (net (code "47") (name "/TFT_Screen_LED") (class "Default")
      (node (ref "U1") (pin "18") (pinfunction "GPIO10/RTC_GPIO10/TOUCH10/ADC1_CH9/FSPICS0/FSPIIO4/SUBSPICS0_18") (pintype "passive"))
    )
    (net (code "48") (name "/TFT_Screen_RESET") (class "Default")
      (node (ref "TP24") (pin "1") (pinfunction "1_1") (pintype "passive"))
      (node (ref "U1") (pin "12") (pinfunction "GPIO8/RTC_GPIO8/TOUCH8/ADC1_CH7/SUBSPICS1_12") (pintype "passive"))
    )
    (net (code "49") (name "/TXD_FTDI") (class "Default")
      (node (ref "R11") (pin "2") (pinfunction "2_2") (pintype "passive"))
      (node (ref "U2") (pin "20") (pinfunction "TXD_20") (pintype "passive"))
    )
    (net (code "50") (name "/Touch_Interrupt_Signal") (class "Default")
      (node (ref "TP30") (pin "1") (pinfunction "1_1") (pintype "passive"))
      (node (ref "U1") (pin "21") (pinfunction "GPIO13/RTC_GPIO13/TOUCH13/ADC2_CH2/FSPIQ/FSPIIO7/SUBSPIQ_21") (pintype "passive"))
    )
    (net (code "51") (name "/Touch_Screen_CS") (class "Default")
      (node (ref "TP21") (pin "1") (pinfunction "1_1") (pintype "passive"))
      (node (ref "U1") (pin "20") (pinfunction "GPIO12/RTC_GPIO12/TOUCH12/ADC2_CH1/FSPICLK/FSPIIO6/SUBSPICLK_20") (pintype "passive"))
    )
    (net (code "52") (name "/U0RXD") (class "Default")
      (node (ref "R11") (pin "1") (pinfunction "1_1") (pintype "passive"))
      (node (ref "U1") (pin "36") (pinfunction "U0RXD/GPIO44CLK_OUT2_36") (pintype "passive"))
    )
    (net (code "53") (name "/U0TXD") (class "Default")
      (node (ref "R12") (pin "1") (pinfunction "1_1") (pintype "passive"))
      (node (ref "U1") (pin "37") (pinfunction "U0TXD/GPIO43/CLK_OUT1_37") (pintype "passive"))
    )
    (net (code "58") (name "/~{ESP_USER_LED}") (class "Default")
      (node (ref "D10") (pin "1") (pinfunction "C_1") (pintype "passive"))
      (node (ref "U1") (pin "8") (pinfunction "GPIO15/RTC_GPIO15/U0RTS/ADC2_CH4/XTAL_32K_P_8") (pintype "passive"))
    )
    (net (code "59") (name "GND") (class "Default")
      (node (ref "C1") (pin "1") (pinfunction "1_1") (pintype "passive"))
      (node (ref "C10") (pin "1") (pinfunction "1_1") (pintype "passive"))
      (node (ref "C11") (pin "1") (pinfunction "1_1") (pintype "passive"))
      (node (ref "C14") (pin "1") (pinfunction "1_1") (pintype "passive"))
      (node (ref "C15") (pin "1") (pinfunction "1_1") (pintype "passive"))
      (node (ref "C16") (pin "1") (pinfunction "1_1") (pintype "passive"))
      (node (ref "C17") (pin "1") (pinfunction "1_1") (pintype "passive"))
      (node (ref "C2") (pin "1") (pinfunction "1_1") (pintype "passive"))
      (node (ref "C3") (pin "1") (pinfunction "1_1") (pintype "passive"))
      (node (ref "C4") (pin "1") (pinfunction "1_1") (pintype "passive"))
      (node (ref "C5") (pin "1") (pinfunction "1_1") (pintype "passive"))
      (node (ref "C7") (pin "1") (pinfunction "1_1") (pintype "passive"))
      (node (ref "C8") (pin "1") (pinfunction "1_1") (pintype "passive"))
      (node (ref "C9") (pin "1") (pinfunction "1_1") (pintype "passive"))
      (node (ref "D3") (pin "2") (pinfunction "2_2") (pintype "passive"))
      (node (ref "D4") (pin "2") (pinfunction "2_2") (pintype "passive"))
      (node (ref "D5") (pin "2") (pinfunction "2_2") (pintype "passive"))
      (node (ref "D6") (pin "2") (pinfunction "2_2") (pintype "passive"))
      (node (ref "D7") (pin "2") (pinfunction "2_2") (pintype "passive"))
      (node (ref "D8") (pin "2") (pinfunction "2_2") (pintype "passive"))
      (node (ref "D9") (pin "1") (pinfunction "C_1") (pintype "passive"))
      (node (ref "J3") (pin "A1-B12") (pinfunction "GND_A1-B12_A1-B12") (pintype "passive"))
      (node (ref "J3") (pin "B1-A12") (pinfunction "GND_B1-A12_B1-A12") (pintype "passive"))
      (node (ref "J3") (pin "S1") (pinfunction "SHIELD_1_S1") (pintype "passive"))
      (node (ref "J3") (pin "S2") (pinfunction "SHIELD_2_S2") (pintype "passive"))
      (node (ref "J3") (pin "S3") (pinfunction "SHIELD_3_S3") (pintype "passive"))
      (node (ref "J3") (pin "S4") (pinfunction "SHIELD_4_S4") (pintype "passive"))
      (node (ref "J4") (pin "A1-B12") (pinfunction "GND_A1-B12_A1-B12") (pintype "passive"))
      (node (ref "J4") (pin "B1-A12") (pinfunction "GND_B1-A12_B1-A12") (pintype "passive"))
      (node (ref "J4") (pin "S1") (pinfunction "SHIELD_1_S1") (pintype "passive"))
      (node (ref "J4") (pin "S2") (pinfunction "SHIELD_2_S2") (pintype "passive"))
      (node (ref "J4") (pin "S3") (pinfunction "SHIELD_3_S3") (pintype "passive"))
      (node (ref "J4") (pin "S4") (pinfunction "SHIELD_4_S4") (pintype "passive"))
      (node (ref "NT8") (pin "2") (pinfunction "10_2") (pintype "passive"))
      (node (ref "R22") (pin "1") (pinfunction "1_1") (pintype "passive"))
      (node (ref "R4") (pin "1") (pinfunction "1_1") (pintype "passive"))
      (node (ref "R5") (pin "1") (pinfunction "1_1") (pintype "passive"))
      (node (ref "R6") (pin "1") (pinfunction "1_1") (pintype "passive"))
      (node (ref "R7") (pin "1") (pinfunction "1_1") (pintype "passive"))
      (node (ref "SW1") (pin "3") (pinfunction "3_3") (pintype "passive"))
      (node (ref "SW1") (pin "4") (pinfunction "4_4") (pintype "passive"))
      (node (ref "SW2") (pin "3") (pinfunction "3_3") (pintype "passive"))
      (node (ref "SW2") (pin "4") (pinfunction "4_4") (pintype "passive"))
      (node (ref "TP3") (pin "1") (pinfunction "1_1") (pintype "passive"))
      (node (ref "TP4") (pin "1") (pinfunction "1_1") (pintype "passive"))
      (node (ref "TP8") (pin "1") (pinfunction "1_1") (pintype "passive"))
      (node (ref "TP9") (pin "1") (pinfunction "1_1") (pintype "passive"))
      (node (ref "U1") (pin "1") (pinfunction "GND_1") (pintype "passive"))
      (node (ref "U1") (pin "40") (pinfunction "GND_40") (pintype "passive"))
      (node (ref "U1") (pin "41") (pinfunction "EPAD_41") (pintype "passive"))
      (node (ref "U2") (pin "16") (pinfunction "GND_16") (pintype "passive"))
      (node (ref "U2") (pin "6") (pinfunction "GND_6") (pintype "passive"))
      (node (ref "U3") (pin "2") (pinfunction "GND_2") (pintype "power_in"))
      (node (ref "U3") (pin "4") (pinfunction "GND_4") (pintype "power_in"))
    )
    (net (code "60") (name "Net-(D10-A)") (class "Default")
      (node (ref "D10") (pin "2") (pinfunction "A_2") (pintype "passive"))
      (node (ref "R14") (pin "1") (pinfunction "1_1") (pintype "passive"))
    )
    (net (code "61") (name "Net-(J3-CC1)") (class "Default")
      (node (ref "J3") (pin "A5") (pinfunction "CC1_A5") (pintype "passive"))
      (node (ref "R7") (pin "2") (pinfunction "2_2") (pintype "passive"))
    )
    (net (code "62") (name "Net-(J3-CC2)") (class "Default")
      (node (ref "J3") (pin "B5") (pinfunction "CC2_B5") (pintype "passive"))
      (node (ref "R6") (pin "2") (pinfunction "2_2") (pintype "passive"))
    )
    (net (code "63") (name "Net-(J4-CC1)") (class "Default")
      (node (ref "J4") (pin "A5") (pinfunction "CC1_A5") (pintype "passive"))
      (node (ref "R5") (pin "2") (pinfunction "2_2") (pintype "passive"))
    )
    (net (code "64") (name "Net-(J4-CC2)") (class "Default")
      (node (ref "J4") (pin "B5") (pinfunction "CC2_B5") (pintype "passive"))
      (node (ref "R4") (pin "2") (pinfunction "2_2") (pintype "passive"))
    )
    (net (code "65") (name "Net-(Q1-B)") (class "Default")
      (node (ref "Q1") (pin "1") (pinfunction "B_1") (pintype "passive"))
      (node (ref "R9") (pin "2") (pinfunction "2_2") (pintype "passive"))
    )
    (net (code "66") (name "Net-(Q2-B)") (class "Default")
      (node (ref "Q2") (pin "1") (pinfunction "B_1") (pintype "passive"))
      (node (ref "R10") (pin "2") (pinfunction "2_2") (pintype "passive"))
    )
    (net (code "67") (name "Net-(U2-~{RESET})") (class "Default")
      (node (ref "R3") (pin "2") (pinfunction "2_2") (pintype "passive"))
      (node (ref "U2") (pin "14") (pinfunction "~{RESET}_14") (pintype "passive"))
    )
    (net (code "68") (name "unconnected-(J3-SBU1-PadA8)") (class "Default")
      (node (ref "J3") (pin "A8") (pinfunction "SBU1_A8") (pintype "passive+no_connect"))
    )
    (net (code "69") (name "unconnected-(J3-SBU2-PadB8)") (class "Default")
      (node (ref "J3") (pin "B8") (pinfunction "SBU2_B8") (pintype "passive+no_connect"))
    )
    (net (code "70") (name "unconnected-(J4-SBU1-PadA8)") (class "Default")
      (node (ref "J4") (pin "A8") (pinfunction "SBU1_A8") (pintype "passive+no_connect"))
    )
    (net (code "71") (name "unconnected-(J4-SBU2-PadB8)") (class "Default")
      (node (ref "J4") (pin "B8") (pinfunction "SBU2_B8") (pintype "passive+no_connect"))
    )
    (net (code "72") (name "unconnected-(U1-GPIO35{slash}SPIIO6{slash}FSPID{slash}SUBSPID-Pad28)") (class "Default")
      (node (ref "U1") (pin "28") (pinfunction "GPIO35/SPIIO6/FSPID/SUBSPID_28") (pintype "passive+no_connect"))
    )
    (net (code "73") (name "unconnected-(U1-GPIO36{slash}SPIIO7{slash}FSPICLK{slash}SUBSPICLK-Pad29)") (class "Default")
      (node (ref "U1") (pin "29") (pinfunction "GPIO36/SPIIO7/FSPICLK/SUBSPICLK_29") (pintype "passive+no_connect"))
    )
    (net (code "74") (name "unconnected-(U1-GPIO37{slash}SPIDQS{slash}FSPIQ{slash}SUBSPIQ-Pad30)") (class "Default")
      (node (ref "U1") (pin "30") (pinfunction "GPIO37/SPIDQS/FSPIQ/SUBSPIQ_30") (pintype "passive+no_connect"))
    )
    (net (code "75") (name "unconnected-(U1-GPIO45-Pad26)") (class "Default")
      (node (ref "U1") (pin "26") (pinfunction "GPIO45_26") (pintype "passive+no_connect"))
    )
    (net (code "76") (name "unconnected-(U1-GPIO46-Pad16)") (class "Default")
      (node (ref "U1") (pin "16") (pinfunction "GPIO46_16") (pintype "passive+no_connect"))
    )
    (net (code "77") (name "unconnected-(U1-GPIO47{slash}SPICLK_P_DIFF{slash}SUBSPICLK_P_DIFF-Pad24)") (class "Default")
      (node (ref "U1") (pin "24") (pinfunction "GPIO47/SPICLK_P_DIFF/SUBSPICLK_P_DIFF_24") (pintype "passive+no_connect"))
    )
    (net (code "78") (name "unconnected-(U1-GPIO48{slash}SPICLK_N_DIFF{slash}SUBSPICLK_N_DIFF-Pad25)") (class "Default")
      (node (ref "U1") (pin "25") (pinfunction "GPIO48/SPICLK_N_DIFF/SUBSPICLK_N_DIFF_25") (pintype "passive+no_connect"))
    )
    (net (code "79") (name "unconnected-(U1-MTCK{slash}GPIO39{slash}CLK_OUT3{slash}SUBSPICS1-Pad32)") (class "Default")
      (node (ref "U1") (pin "32") (pinfunction "MTCK/GPIO39/CLK_OUT3/SUBSPICS1_32") (pintype "passive+no_connect"))
    )
    (net (code "80") (name "unconnected-(U1-MTDI{slash}GPIO41{slash}CLK_OUT1-Pad34)") (class "Default")
      (node (ref "U1") (pin "34") (pinfunction "MTDI/GPIO41/CLK_OUT1_34") (pintype "passive"))
    )
    (net (code "81") (name "unconnected-(U1-MTMS{slash}GPIO42-Pad35)") (class "Default")
      (node (ref "U1") (pin "35") (pinfunction "MTMS/GPIO42_35") (pintype "passive"))
    )
    (net (code "82") (name "unconnected-(U2-CBUS0-Pad18)") (class "Default")
      (node (ref "U2") (pin "18") (pinfunction "CBUS0_18") (pintype "passive+no_connect"))
    )
    (net (code "83") (name "unconnected-(U2-CBUS1-Pad17)") (class "Default")
      (node (ref "U2") (pin "17") (pinfunction "CBUS1_17") (pintype "passive+no_connect"))
    )
    (net (code "84") (name "unconnected-(U2-CBUS2-Pad10)") (class "Default")
      (node (ref "U2") (pin "10") (pinfunction "CBUS2_10") (pintype "passive+no_connect"))
    )
    (net (code "85") (name "unconnected-(U2-CBUS3-Pad19)") (class "Default")
      (node (ref "U2") (pin "19") (pinfunction "CBUS3_19") (pintype "passive+no_connect"))
    )
    (net (code "86") (name "unconnected-(U2-~{CTS}-Pad9)") (class "Default")
      (node (ref "U2") (pin "9") (pinfunction "~{CTS}_9") (pintype "passive+no_connect"))
    )
    (net (code "87") (name "unconnected-(U2-~{DCD}-Pad8)") (class "Default")
      (node (ref "U2") (pin "8") (pinfunction "~{DCD}_8") (pintype "passive+no_connect"))
    )
    (net (code "88") (name "unconnected-(U2-~{DSR}-Pad7)") (class "Default")
      (node (ref "U2") (pin "7") (pinfunction "~{DSR}_7") (pintype "passive+no_connect"))
    )
    (net (code "89") (name "unconnected-(U2-~{RI}-Pad5)") (class "Default")
      (node (ref "U2") (pin "5") (pinfunction "~{RI}_5") (pintype "passive+no_connect"))
    )
  )
)
